# gauntlet.net
KiCad netlist of a schematic drawn in Altium Designer
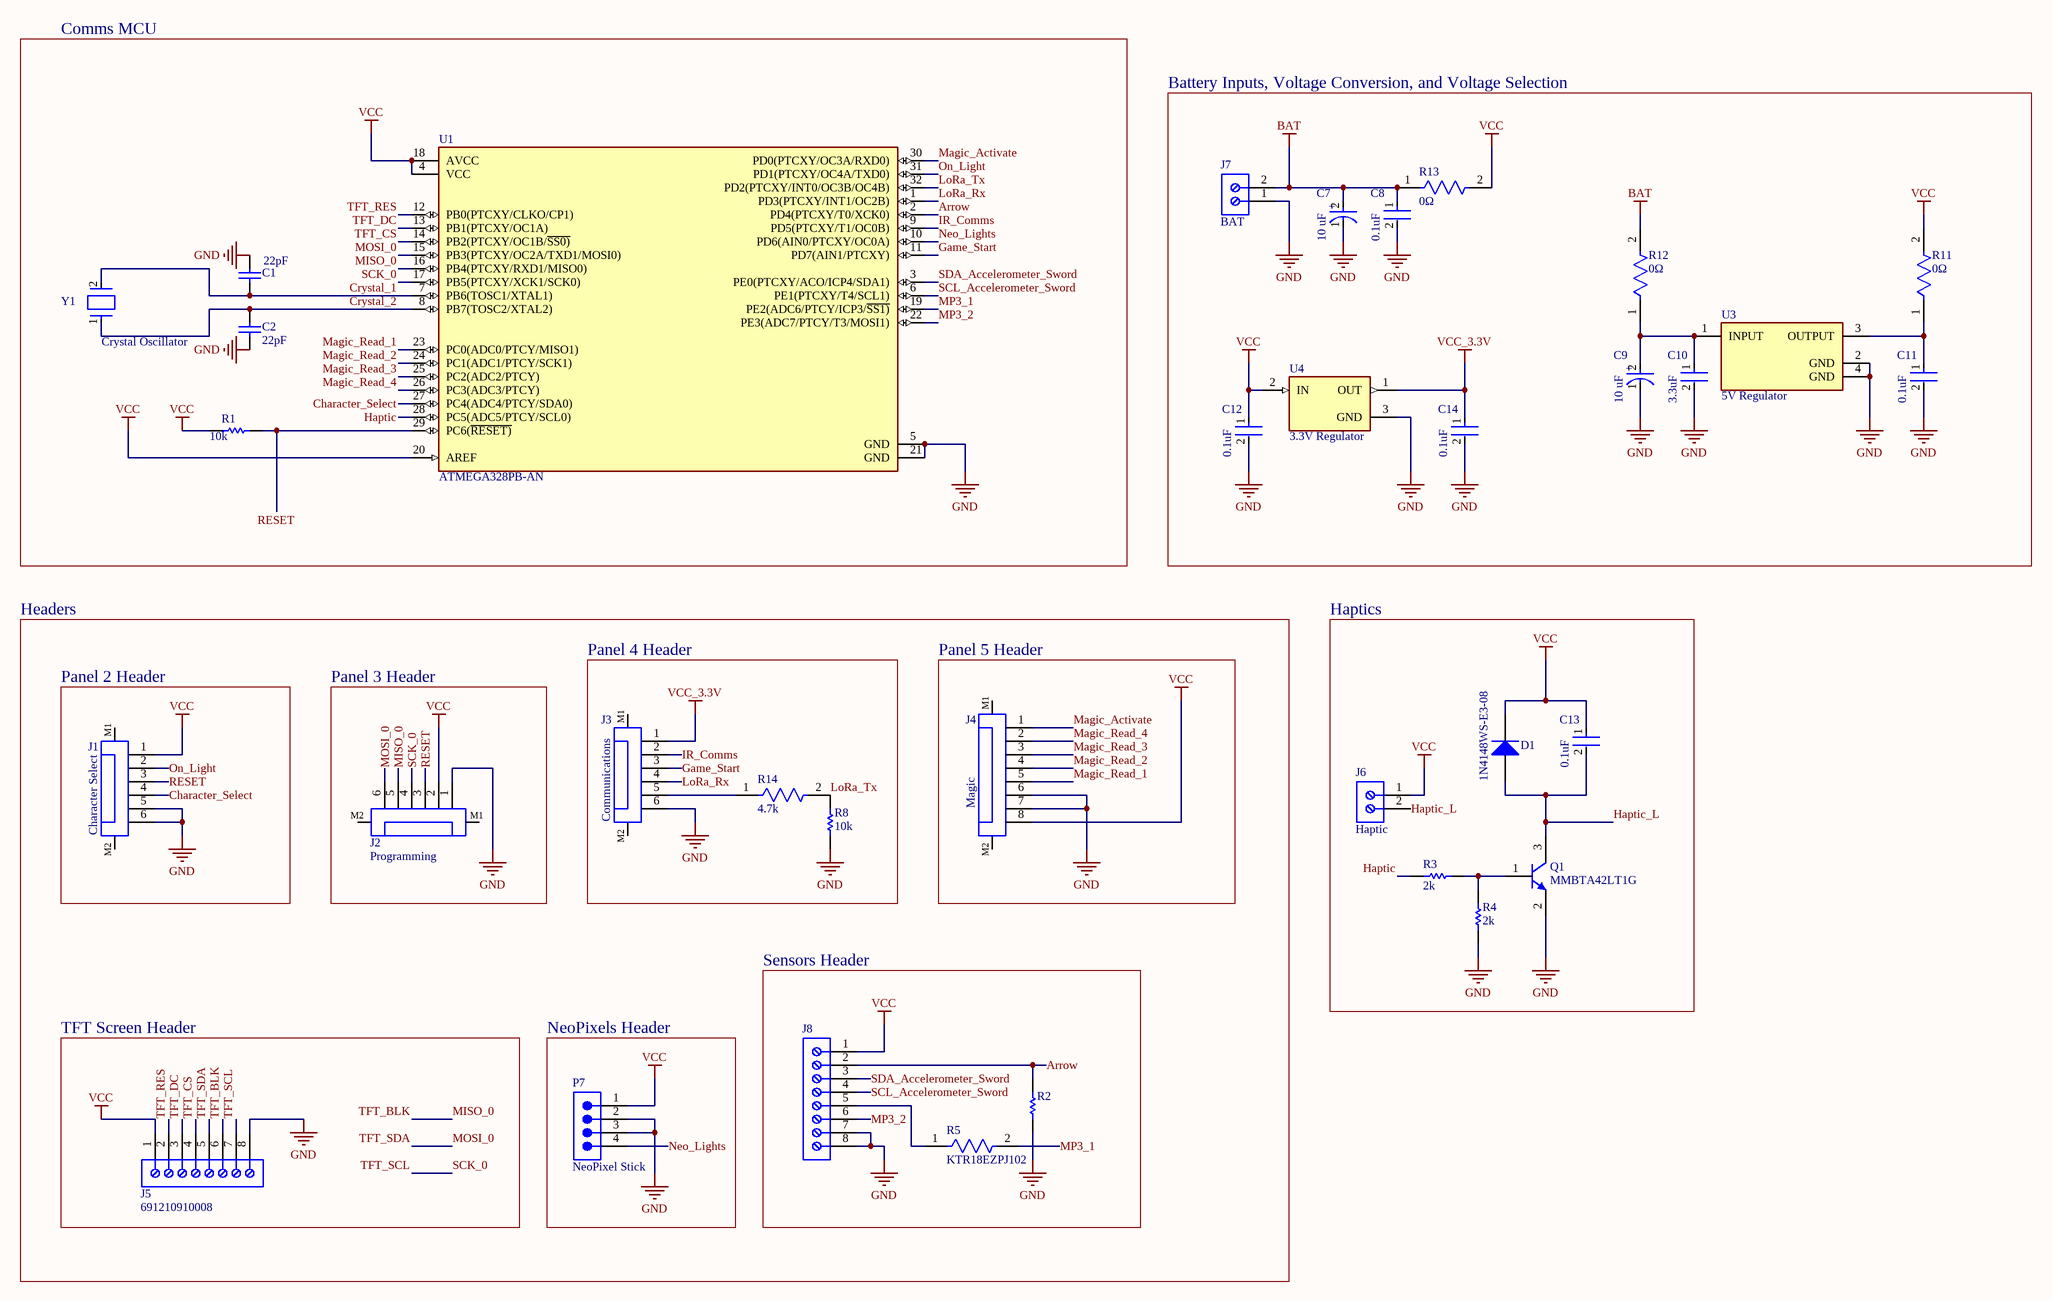
[diagram p0: gauntlet.SchDoc]

(export (version "E")
  (design (tool "Eeschema 10.0.6"))
  (components
    (comp (ref "C1")
      (value "22pF")
      (footprint "WCAP-CSGP_1206_L3.2W1.6H0.8")
      (fields (field (name "TOLERANCE") "5%"))
      (libsource (lib "Altium Content Vault") (part "Capacitor_Non-Polarized"))
    )
    (comp (ref "C2")
      (value "22pF")
      (footprint "WCAP-CSGP_1206_L3.2W1.6H0.8")
      (fields (field (name "TOLERANCE") "5%"))
      (libsource (lib "Altium Content Vault") (part "Capacitor_Non-Polarized"))
    )
    (comp (ref "C7")
      (value "10 uF")
      (footprint "FP-FTB-MFG")
      (description "CAP ALUM 10UF 20% 50V SMD")
      (fields (field (name "VOLTAGE") "50V") (field (name "TOLERANCE") "20%"))
      (libsource (lib "Altium Content Vault") (part "a00bbbee19879c290e62620ae7e47b1"))
    )
    (comp (ref "C8")
      (value "0.1uF")
      (footprint "FP-GRM31M-0_15-IPC_A")
      (fields (field (name "VOLTAGE") "50V") (field (name "TOLERANCE") "5%"))
      (libsource (lib "Altium Content Vault") (part "b4654b650e69147ec39a6b967a45e02"))
    )
    (comp (ref "C9")
      (value "10 uF")
      (footprint "FP-FTB-MFG")
      (description "CAP ALUM 10UF 20% 50V SMD")
      (fields (field (name "VOLTAGE") "50V") (field (name "TOLERANCE") "20%"))
      (libsource (lib "Altium Content Vault") (part "a00bbbee19879c290e62620ae7e47b1"))
    )
    (comp (ref "C10")
      (value "3.3uF")
      (footprint "FP-GCG31C-0_3-IPC_B")
      (libsource (lib "Altium Content Vault") (part "02cd4be3c70576c341d710602a673aa"))
    )
    (comp (ref "C11")
      (value "0.1uF")
      (footprint "FP-GRM31M-0_15-IPC_A")
      (fields (field (name "VOLTAGE") "50V") (field (name "TOLERANCE") "5%"))
      (libsource (lib "Altium Content Vault") (part "b4654b650e69147ec39a6b967a45e02"))
    )
    (comp (ref "C12")
      (value "0.1uF")
      (footprint "FP-GRM31M-0_15-IPC_A")
      (fields (field (name "VOLTAGE") "50V") (field (name "TOLERANCE") "5%"))
      (libsource (lib "Altium Content Vault") (part "b4654b650e69147ec39a6b967a45e02"))
    )
    (comp (ref "C13")
      (value "0.1uF")
      (footprint "FP-GRM31M-0_15-IPC_A")
      (fields (field (name "VOLTAGE") "50V") (field (name "TOLERANCE") "5%"))
      (libsource (lib "Altium Content Vault") (part "b4654b650e69147ec39a6b967a45e02"))
    )
    (comp (ref "C14")
      (value "0.1uF")
      (footprint "FP-GRM31M-0_15-IPC_A")
      (fields (field (name "VOLTAGE") "50V") (field (name "TOLERANCE") "5%"))
      (libsource (lib "Altium Content Vault") (part "b4654b650e69147ec39a6b967a45e02"))
    )
    (comp (ref "D1")
      (value "1N4148WS-E3-08")
      (footprint "VISH-SOD-323-2_V")
      (fields (field (name "MANUFACTURER") "Vishay"))
      (libsource (lib "Altium Content Vault") (part "D-AK-2"))
    )
    (comp (ref "J1")
      (value "Character Select")
      (footprint "686106183422")
      (description "686106183422")
      (libsource (lib "Altium Content Vault") (part "FPC - 06P - 2MP"))
    )
    (comp (ref "J2")
      (value "Programming")
      (footprint "686106183422")
      (description "686106183422")
      (libsource (lib "Altium Content Vault") (part "FPC - 06P - 2MP"))
    )
    (comp (ref "J3")
      (value "Communications")
      (footprint "686106183422")
      (description "686106183422")
      (libsource (lib "Altium Content Vault") (part "FPC - 06P - 2MP"))
    )
    (comp (ref "J4")
      (value "Magic")
      (footprint "686108183422")
      (description "686108183422")
      (libsource (lib "Altium Content Vault") (part "FPC - 08P - 2MP"))
    )
    (comp (ref "J5")
      (value "691210910008")
      (footprint "691210910008")
      (libsource (lib "Altium Content Vault") (part "TBL - 1R - 08P - Screw"))
    )
    (comp (ref "J6")
      (value "Haptic")
      (footprint "691210910002")
      (description "691210910002")
      (libsource (lib "Altium Content Vault") (part "TBL - 1R - 02P - Screw"))
    )
    (comp (ref "J7")
      (value "BAT")
      (footprint "691210910002")
      (description "691210910002")
      (libsource (lib "Altium Content Vault") (part "TBL - 1R - 02P - Screw"))
    )
    (comp (ref "J8")
      (value "~")
      (footprint "691210910008")
      (description "691210910008")
      (libsource (lib "Altium Content Vault") (part "TBL - 1R - 08P - Screw"))
    )
    (comp (ref "P7")
      (value "NeoPixel Stick")
      (footprint "61300411121")
      (description "61300411121")
      (libsource (lib "Altium Content Vault") (part "Header_Male_1R_04P"))
    )
    (comp (ref "Q1")
      (value "MMBTA42LT1G")
      (footprint "ONSC-SOT-23-3-318-08_V")
      (description "High Voltage Transistor, NPN Silicon, 3-Pin SOT-23, Pb-Free, Tape and Reel")
      (fields (field (name "MANUFACTURER") "On Semiconductor"))
      (libsource (lib "Altium Content Vault") (part "ONSC-NPN-B1E2C3-3"))
    )
    (comp (ref "R1")
      (value "10k")
      (footprint "RESC3116X65X40ML10T20")
      (description "Chip Resistor, 10 KOhm, +/- 1%, 0.25 W, -55 to 155 degC, 1206 (3216 Metric), RoHS, Tape and Reel")
      (fields (field (name "TOLERANCE") "1%") (field (name "MANUFACTURER") "Yageo"))
      (libsource (lib "Altium Content Vault") (part "RES-2"))
    )
    (comp (ref "R2")
      (value "~")
      (footprint "RESC3116X65X40LL10T20")
      (description "RC1206JR-10220RL")
      (fields (field (name "MANUFACTURER") "Yageo"))
      (libsource (lib "Altium Content Vault") (part "RES"))
    )
    (comp (ref "R3")
      (value "2k")
      (footprint "RESC3116X65X40LL10T20")
      (description "RT1206BRD072KL")
      (fields (field (name "MANUFACTURER") "Yageo"))
      (libsource (lib "Altium Content Vault") (part "RES"))
    )
    (comp (ref "R4")
      (value "2k")
      (footprint "RESC3116X65X40LL10T20")
      (description "RT1206BRD072KL")
      (fields (field (name "MANUFACTURER") "Yageo"))
      (libsource (lib "Altium Content Vault") (part "RES"))
    )
    (comp (ref "R5")
      (value "KTR18EZPJ102")
      (footprint "FP-KTR18-IPC_A")
      (description "Res Thick Film 1206 1kΩ 5% 0.1W ±200ppm/°C Automotive Paper T/R")
      (fields (field (name "TOLERANCE") "5%"))
      (libsource (lib "Altium Content Vault") (part "1029c3af85768c4190bb7ad29bc67b5"))
    )
    (comp (ref "R8")
      (value "10k")
      (footprint "RESC3116X65X40ML10T20")
      (fields (field (name "MANUFACTURER") "Yageo") (field (name "PART NUMBER") "RC1206JR-1310KL"))
      (libsource (lib "Altium Content Vault") (part "RES"))
    )
    (comp (ref "R11")
      (value "0Ω")
      (footprint "FP-CR1206-MFG")
      (description "CR1206-J/-000ELF\r\nThick Film Chip Resistors 1206 0Ω 0.25W 5%")
      (fields (field (name "TOLERANCE") "5%"))
      (libsource (lib "Altium Content Vault") (part "1029c3af85768c4190bb7ad29bc67b5"))
    )
    (comp (ref "R12")
      (value "0Ω")
      (footprint "FP-CR1206-MFG")
      (description "CR1206-J/-000ELF\r\nThick Film Chip Resistors 1206 0Ω 0.25W 5%")
      (fields (field (name "TOLERANCE") "5%"))
      (libsource (lib "Altium Content Vault") (part "1029c3af85768c4190bb7ad29bc67b5"))
    )
    (comp (ref "R13")
      (value "0Ω")
      (footprint "FP-CR1206-MFG")
      (description "CR1206-J/-000ELF\r\nThick Film Chip Resistors 1206 0Ω 0.25W 5%")
      (fields (field (name "TOLERANCE") "5%"))
      (libsource (lib "Altium Content Vault") (part "1029c3af85768c4190bb7ad29bc67b5"))
    )
    (comp (ref "R14")
      (value "4.7k")
      (footprint "FP-RT1206-MFG")
      (description "RT1206BRD074K7L\r\nRES SMD 4.7K OHM 0.1% 1/4W 1206")
      (fields
        (field (name "TOLERANCE") "0.005")
        (field (name "OCTOPART") "https://octopart.com/rt1206brd074k7l-yageo-1170071")
      )
      (libsource (lib "Altium Content Vault") (part "1029c3af85768c4190bb7ad29bc67b5"))
    )
    (comp (ref "U1")
      (value "ATMEGA328PB-AN")
      (footprint "FP-C04-074-MFG")
      (description "IC MCU 8BIT 32KB FLASH 32TQFP")
      (fields
        (field (name "MANUFACTURER") "Microchip")
        (field (name "OCTOPART") "https://octopart.com/atmega328pb-an-microchip-77760226")
      )
      (libsource (lib "Altium Content Vault") (part "90de4778911676f39d877d46b6c1e42"))
    )
    (comp (ref "U3")
      (value "5V Regulator")
      (footprint "FP-LM7805MPX-NOPB-MFG")
      (description "IC REG LINEAR 5V 1.5A SOT223-4\r\nLM7805")
      (fields
        (field (name "MANUFACTURER") "Texas Instruments")
        (field (name "MANUFACTURER PART NUMBER") "LM7805MPX/NOPB")
      )
      (libsource (lib "Altium Content Vault") (part "b4ee7691a89d8e73302b24c49f391f2"))
    )
    (comp (ref "U4")
      (value "3.3V Regulator")
      (footprint "FP-DBZ0003A-MFG")
      (description "TLV76033DBZR\r\nIC REG LINEAR 3.3V 100MA SOT23-3")
      (fields
        (field (name "OCTOPART") "https://octopart.com/tlv76033dbzr-texas+instruments-84352145")
        (field (name "MANUFACTURER PART NUMBER") "TLV76033DBZR")
      )
      (libsource (lib "Altium Content Vault") (part "530f02c4486e1a9cf177a64aa0b0e10"))
    )
    (comp (ref "Y1")
      (value "Crystal Oscillator")
      (footprint "FP-ABM3-MFG")
      (description "ABM3-16.000MHZ-D2Y-T\r\nCrystal 16MHz ±20ppm 18pF SMD-2 5mm x 3.2mm")
      (fields (field (name "TOLERANCE") "20ppm"))
      (libsource (lib "Altium Content Vault") (part "c23a69dc6c9e2f18f2079038eb95dd1"))
    )
  )
  (nets
    (net (code "1") (name "/Arrow") (class "Default")
      (node (ref "J8") (pin "2") (pinfunction "2_2") (pintype "passive"))
      (node (ref "R2") (pin "2") (pinfunction "2_2") (pintype "passive"))
      (node (ref "U1") (pin "2") (pinfunction "PD4(PTCXY/T0/XCK0)_2") (pintype "bidirectional"))
    )
    (net (code "2") (name "/Character_Select") (class "Default")
      (node (ref "J1") (pin "4") (pinfunction "4_4") (pintype "passive"))
      (node (ref "U1") (pin "27") (pinfunction "PC4(ADC4/PTCY/SDA0)_27") (pintype "bidirectional"))
    )
    (net (code "3") (name "/Crystal_1") (class "Default")
      (node (ref "C1") (pin "1") (pinfunction "1_1") (pintype "passive"))
      (node (ref "U1") (pin "7") (pinfunction "PB6(TOSC1/XTAL1)_7") (pintype "bidirectional"))
      (node (ref "Y1") (pin "2") (pinfunction "2_2") (pintype "passive"))
    )
    (net (code "4") (name "/Crystal_2") (class "Default")
      (node (ref "C2") (pin "2") (pinfunction "2_2") (pintype "passive"))
      (node (ref "U1") (pin "8") (pinfunction "PB7(TOSC2/XTAL2)_8") (pintype "bidirectional"))
      (node (ref "Y1") (pin "1") (pinfunction "1_1") (pintype "passive"))
    )
    (net (code "5") (name "/Game_Start") (class "Default")
      (node (ref "J3") (pin "3") (pinfunction "3_3") (pintype "passive"))
      (node (ref "U1") (pin "11") (pinfunction "PD7(AIN1/PTCXY)_11") (pintype "bidirectional"))
    )
    (net (code "6") (name "/Haptic") (class "Default")
      (node (ref "R3") (pin "2") (pinfunction "2_2") (pintype "passive"))
      (node (ref "U1") (pin "28") (pinfunction "PC5(ADC5/PTCY/SCL0)_28") (pintype "bidirectional"))
    )
    (net (code "7") (name "/Haptic_L") (class "Default")
      (node (ref "C13") (pin "2") (pinfunction "2_2") (pintype "passive"))
      (node (ref "D1") (pin "1") (pinfunction "A_1") (pintype "passive"))
      (node (ref "J6") (pin "2") (pinfunction "2_2") (pintype "passive"))
      (node (ref "Q1") (pin "3") (pinfunction "C_3") (pintype "passive"))
    )
    (net (code "8") (name "/IR_Comms") (class "Default")
      (node (ref "J3") (pin "2") (pinfunction "2_2") (pintype "passive"))
      (node (ref "U1") (pin "9") (pinfunction "PD5(PTCXY/T1/OC0B)_9") (pintype "bidirectional"))
    )
    (net (code "9") (name "/LoRa_Rx") (class "Default")
      (node (ref "J3") (pin "4") (pinfunction "4_4") (pintype "passive"))
      (node (ref "U1") (pin "1") (pinfunction "PD3(PTCXY/INT1/OC2B)_1") (pintype "bidirectional"))
    )
    (net (code "10") (name "/LoRa_Tx") (class "Default")
      (node (ref "R14") (pin "2") (pinfunction "2_2") (pintype "passive"))
      (node (ref "R8") (pin "2") (pinfunction "2_2") (pintype "passive"))
      (node (ref "U1") (pin "32") (pinfunction "PD2(PTCXY/INT0/OC3B/OC4B)_32") (pintype "bidirectional"))
    )
    (net (code "11") (name "/MISO_0") (class "Default")
      (node (ref "J2") (pin "5") (pinfunction "5_5") (pintype "passive"))
      (node (ref "J5") (pin "6") (pinfunction "6_6") (pintype "passive"))
      (node (ref "U1") (pin "16") (pinfunction "PB4(PTCXY/RXD1/MISO0)_16") (pintype "bidirectional"))
    )
    (net (code "12") (name "/MOSI_0") (class "Default")
      (node (ref "J2") (pin "6") (pinfunction "6_6") (pintype "passive"))
      (node (ref "J5") (pin "5") (pinfunction "5_5") (pintype "passive"))
      (node (ref "U1") (pin "15") (pinfunction "PB3(PTCXY/OC2A/TXD1/MOSI0)_15") (pintype "bidirectional"))
    )
    (net (code "13") (name "/MP3_1") (class "Default")
      (node (ref "R5") (pin "2") (pinfunction "2_2") (pintype "passive"))
      (node (ref "U1") (pin "19") (pinfunction "PE2(ADC6/PTCY/ICP3/~{SS1)}_19") (pintype "bidirectional"))
    )
    (net (code "14") (name "/MP3_2") (class "Default")
      (node (ref "J8") (pin "6") (pinfunction "6_6") (pintype "passive"))
      (node (ref "U1") (pin "22") (pinfunction "PE3(ADC7/PTCY/T3/MOSI1)_22") (pintype "bidirectional"))
    )
    (net (code "15") (name "/Magic_Activate") (class "Default")
      (node (ref "J4") (pin "1") (pinfunction "1_1") (pintype "passive"))
      (node (ref "U1") (pin "30") (pinfunction "PD0(PTCXY/OC3A/RXD0)_30") (pintype "bidirectional"))
    )
    (net (code "16") (name "/Magic_Read_1") (class "Default")
      (node (ref "J4") (pin "5") (pinfunction "5_5") (pintype "passive"))
      (node (ref "U1") (pin "23") (pinfunction "PC0(ADC0/PTCY/MISO1)_23") (pintype "bidirectional"))
    )
    (net (code "17") (name "/Magic_Read_2") (class "Default")
      (node (ref "J4") (pin "4") (pinfunction "4_4") (pintype "passive"))
      (node (ref "U1") (pin "24") (pinfunction "PC1(ADC1/PTCY/SCK1)_24") (pintype "bidirectional"))
    )
    (net (code "18") (name "/Magic_Read_3") (class "Default")
      (node (ref "J4") (pin "3") (pinfunction "3_3") (pintype "passive"))
      (node (ref "U1") (pin "25") (pinfunction "PC2(ADC2/PTCY)_25") (pintype "bidirectional"))
    )
    (net (code "19") (name "/Magic_Read_4") (class "Default")
      (node (ref "J4") (pin "2") (pinfunction "2_2") (pintype "passive"))
      (node (ref "U1") (pin "26") (pinfunction "PC3(ADC3/PTCY)_26") (pintype "bidirectional"))
    )
    (net (code "20") (name "/Neo_Lights") (class "Default")
      (node (ref "P7") (pin "4") (pinfunction "4_4") (pintype "passive"))
      (node (ref "U1") (pin "10") (pinfunction "PD6(AIN0/PTCXY/OC0A)_10") (pintype "bidirectional"))
    )
    (net (code "21") (name "/On_Light") (class "Default")
      (node (ref "J1") (pin "2") (pinfunction "2_2") (pintype "passive"))
      (node (ref "U1") (pin "31") (pinfunction "PD1(PTCXY/OC4A/TXD0)_31") (pintype "bidirectional"))
    )
    (net (code "22") (name "/RESET") (class "Default")
      (node (ref "J1") (pin "3") (pinfunction "3_3") (pintype "passive"))
      (node (ref "J2") (pin "3") (pinfunction "3_3") (pintype "passive"))
      (node (ref "R1") (pin "2") (pinfunction "2_2") (pintype "passive"))
      (node (ref "U1") (pin "29") (pinfunction "PC6(~{RESET)}_29") (pintype "bidirectional"))
    )
    (net (code "23") (name "/SCK_0") (class "Default")
      (node (ref "J2") (pin "4") (pinfunction "4_4") (pintype "passive"))
      (node (ref "J5") (pin "7") (pinfunction "7_7") (pintype "passive"))
      (node (ref "U1") (pin "17") (pinfunction "PB5(PTCXY/XCK1/SCK0)_17") (pintype "bidirectional"))
    )
    (net (code "24") (name "/SCL_Accelerometer_Sword") (class "Default")
      (node (ref "J8") (pin "4") (pinfunction "4_4") (pintype "passive"))
      (node (ref "U1") (pin "6") (pinfunction "PE1(PTCXY/T4/SCL1)_6") (pintype "bidirectional"))
    )
    (net (code "25") (name "/SDA_Accelerometer_Sword") (class "Default")
      (node (ref "J8") (pin "3") (pinfunction "3_3") (pintype "passive"))
      (node (ref "U1") (pin "3") (pinfunction "PE0(PTCXY/ACO/ICP4/SDA1)_3") (pintype "bidirectional"))
    )
    (net (code "26") (name "/TFT_CS") (class "Default")
      (node (ref "J5") (pin "4") (pinfunction "4_4") (pintype "passive"))
      (node (ref "U1") (pin "14") (pinfunction "PB2(PTCXY/OC1B/~{SS0)}_14") (pintype "bidirectional"))
    )
    (net (code "27") (name "/TFT_DC") (class "Default")
      (node (ref "J5") (pin "3") (pinfunction "3_3") (pintype "passive"))
      (node (ref "U1") (pin "13") (pinfunction "PB1(PTCXY/OC1A)_13") (pintype "bidirectional"))
    )
    (net (code "28") (name "/TFT_RES") (class "Default")
      (node (ref "J5") (pin "2") (pinfunction "2_2") (pintype "passive"))
      (node (ref "U1") (pin "12") (pinfunction "PB0(PTCXY/CLKO/CP1)_12") (pintype "bidirectional"))
    )
    (net (code "29") (name "BAT") (class "Default")
      (node (ref "C7") (pin "2") (pinfunction "A_2") (pintype "passive"))
      (node (ref "C8") (pin "1") (pinfunction "1_1") (pintype "passive"))
      (node (ref "J7") (pin "2") (pinfunction "2_2") (pintype "passive"))
      (node (ref "R12") (pin "2") (pinfunction "2_2") (pintype "passive"))
      (node (ref "R13") (pin "1") (pinfunction "1_1") (pintype "passive"))
    )
    (net (code "30") (name "GND") (class "Default")
      (node (ref "C1") (pin "2") (pinfunction "2_2") (pintype "passive"))
      (node (ref "C10") (pin "2") (pinfunction "2_2") (pintype "passive"))
      (node (ref "C11") (pin "2") (pinfunction "2_2") (pintype "passive"))
      (node (ref "C12") (pin "2") (pinfunction "2_2") (pintype "passive"))
      (node (ref "C14") (pin "2") (pinfunction "2_2") (pintype "passive"))
      (node (ref "C2") (pin "1") (pinfunction "1_1") (pintype "passive"))
      (node (ref "C7") (pin "1") (pinfunction "C_1") (pintype "passive"))
      (node (ref "C8") (pin "2") (pinfunction "2_2") (pintype "passive"))
      (node (ref "C9") (pin "1") (pinfunction "C_1") (pintype "passive"))
      (node (ref "J1") (pin "5") (pinfunction "5_5") (pintype "passive"))
      (node (ref "J1") (pin "6") (pinfunction "6_6") (pintype "passive"))
      (node (ref "J2") (pin "1") (pinfunction "1_1") (pintype "passive"))
      (node (ref "J3") (pin "6") (pinfunction "6_6") (pintype "passive"))
      (node (ref "J4") (pin "6") (pinfunction "6_6") (pintype "passive"))
      (node (ref "J4") (pin "7") (pinfunction "7_7") (pintype "passive"))
      (node (ref "J5") (pin "8") (pinfunction "8_8") (pintype "passive"))
      (node (ref "J7") (pin "1") (pinfunction "1_1") (pintype "passive"))
      (node (ref "J8") (pin "7") (pinfunction "7_7") (pintype "passive"))
      (node (ref "J8") (pin "8") (pinfunction "8_8") (pintype "passive"))
      (node (ref "P7") (pin "2") (pinfunction "2_2") (pintype "passive"))
      (node (ref "P7") (pin "3") (pinfunction "3_3") (pintype "passive"))
      (node (ref "Q1") (pin "2") (pinfunction "E_2") (pintype "passive"))
      (node (ref "R2") (pin "1") (pinfunction "1_1") (pintype "passive"))
      (node (ref "R4") (pin "1") (pinfunction "1_1") (pintype "passive"))
      (node (ref "R8") (pin "1") (pinfunction "1_1") (pintype "passive"))
      (node (ref "U1") (pin "21") (pinfunction "GND_21") (pintype "power_in"))
      (node (ref "U1") (pin "5") (pinfunction "GND_5") (pintype "power_in"))
      (node (ref "U3") (pin "2") (pinfunction "GND_2") (pintype "power_in"))
      (node (ref "U3") (pin "4") (pinfunction "GND_4") (pintype "power_in"))
      (node (ref "U4") (pin "3") (pinfunction "GND_3") (pintype "power_in"))
    )
    (net (code "31") (name "Net-(C9-A)") (class "Default")
      (node (ref "C10") (pin "1") (pinfunction "1_1") (pintype "passive"))
      (node (ref "C9") (pin "2") (pinfunction "A_2") (pintype "passive"))
      (node (ref "R12") (pin "1") (pinfunction "1_1") (pintype "passive"))
      (node (ref "U3") (pin "1") (pinfunction "INPUT_1") (pintype "power_in"))
    )
    (net (code "32") (name "Net-(J3-Pad5)") (class "Default")
      (node (ref "J3") (pin "5") (pinfunction "5_5") (pintype "passive"))
      (node (ref "R14") (pin "1") (pinfunction "1_1") (pintype "passive"))
    )
    (net (code "33") (name "Net-(J8-Pad5)") (class "Default")
      (node (ref "J8") (pin "5") (pinfunction "5_5") (pintype "passive"))
      (node (ref "R5") (pin "1") (pinfunction "1_1") (pintype "passive"))
    )
    (net (code "34") (name "Net-(Q1-B)") (class "Default")
      (node (ref "Q1") (pin "1") (pinfunction "B_1") (pintype "passive"))
      (node (ref "R3") (pin "1") (pinfunction "1_1") (pintype "passive"))
      (node (ref "R4") (pin "2") (pinfunction "2_2") (pintype "passive"))
    )
    (net (code "35") (name "Net-(U3-OUTPUT)") (class "Default")
      (node (ref "C11") (pin "1") (pinfunction "1_1") (pintype "passive"))
      (node (ref "R11") (pin "1") (pinfunction "1_1") (pintype "passive"))
      (node (ref "U3") (pin "3") (pinfunction "OUTPUT_3") (pintype "passive"))
    )
    (net (code "36") (name "VCC") (class "Default")
      (node (ref "C12") (pin "1") (pinfunction "1_1") (pintype "passive"))
      (node (ref "C13") (pin "1") (pinfunction "1_1") (pintype "passive"))
      (node (ref "D1") (pin "2") (pinfunction "K_2") (pintype "passive"))
      (node (ref "J1") (pin "1") (pinfunction "1_1") (pintype "passive"))
      (node (ref "J2") (pin "2") (pinfunction "2_2") (pintype "passive"))
      (node (ref "J4") (pin "8") (pinfunction "8_8") (pintype "passive"))
      (node (ref "J5") (pin "1") (pinfunction "1_1") (pintype "passive"))
      (node (ref "J6") (pin "1") (pinfunction "1_1") (pintype "passive"))
      (node (ref "J8") (pin "1") (pinfunction "1_1") (pintype "passive"))
      (node (ref "P7") (pin "1") (pinfunction "1_1") (pintype "passive"))
      (node (ref "R1") (pin "1") (pinfunction "1_1") (pintype "passive"))
      (node (ref "R11") (pin "2") (pinfunction "2_2") (pintype "passive"))
      (node (ref "R13") (pin "2") (pinfunction "2_2") (pintype "passive"))
      (node (ref "U1") (pin "18") (pinfunction "AVCC_18") (pintype "power_in"))
      (node (ref "U1") (pin "20") (pinfunction "AREF_20") (pintype "input"))
      (node (ref "U1") (pin "4") (pinfunction "VCC_4") (pintype "power_in"))
      (node (ref "U4") (pin "2") (pinfunction "IN_2") (pintype "input"))
    )
    (net (code "37") (name "VCC_3.3V") (class "Default")
      (node (ref "C14") (pin "1") (pinfunction "1_1") (pintype "passive"))
      (node (ref "J3") (pin "1") (pinfunction "1_1") (pintype "passive"))
      (node (ref "U4") (pin "1") (pinfunction "OUT_1") (pintype "output"))
    )
    (net (code "38") (name "unconnected-(J1-PadM1)") (class "Default")
      (node (ref "J1") (pin "M1") (pinfunction "M1_M1") (pintype "passive"))
    )
    (net (code "39") (name "unconnected-(J1-PadM2)") (class "Default")
      (node (ref "J1") (pin "M2") (pinfunction "M2_M2") (pintype "passive"))
    )
    (net (code "40") (name "unconnected-(J2-PadM1)") (class "Default")
      (node (ref "J2") (pin "M1") (pinfunction "M1_M1") (pintype "passive"))
    )
    (net (code "41") (name "unconnected-(J2-PadM2)") (class "Default")
      (node (ref "J2") (pin "M2") (pinfunction "M2_M2") (pintype "passive"))
    )
    (net (code "42") (name "unconnected-(J3-PadM1)") (class "Default")
      (node (ref "J3") (pin "M1") (pinfunction "M1_M1") (pintype "passive"))
    )
    (net (code "43") (name "unconnected-(J3-PadM2)") (class "Default")
      (node (ref "J3") (pin "M2") (pinfunction "M2_M2") (pintype "passive"))
    )
    (net (code "44") (name "unconnected-(J4-PadM1)") (class "Default")
      (node (ref "J4") (pin "M1") (pinfunction "M1_M1") (pintype "passive"))
    )
    (net (code "45") (name "unconnected-(J4-PadM2)") (class "Default")
      (node (ref "J4") (pin "M2") (pinfunction "M2_M2") (pintype "passive"))
    )
  )
)
